# feather-power-switch-i2c-spi-breakout-mk.net
KiCad netlist of a schematic drawn in EAGLE
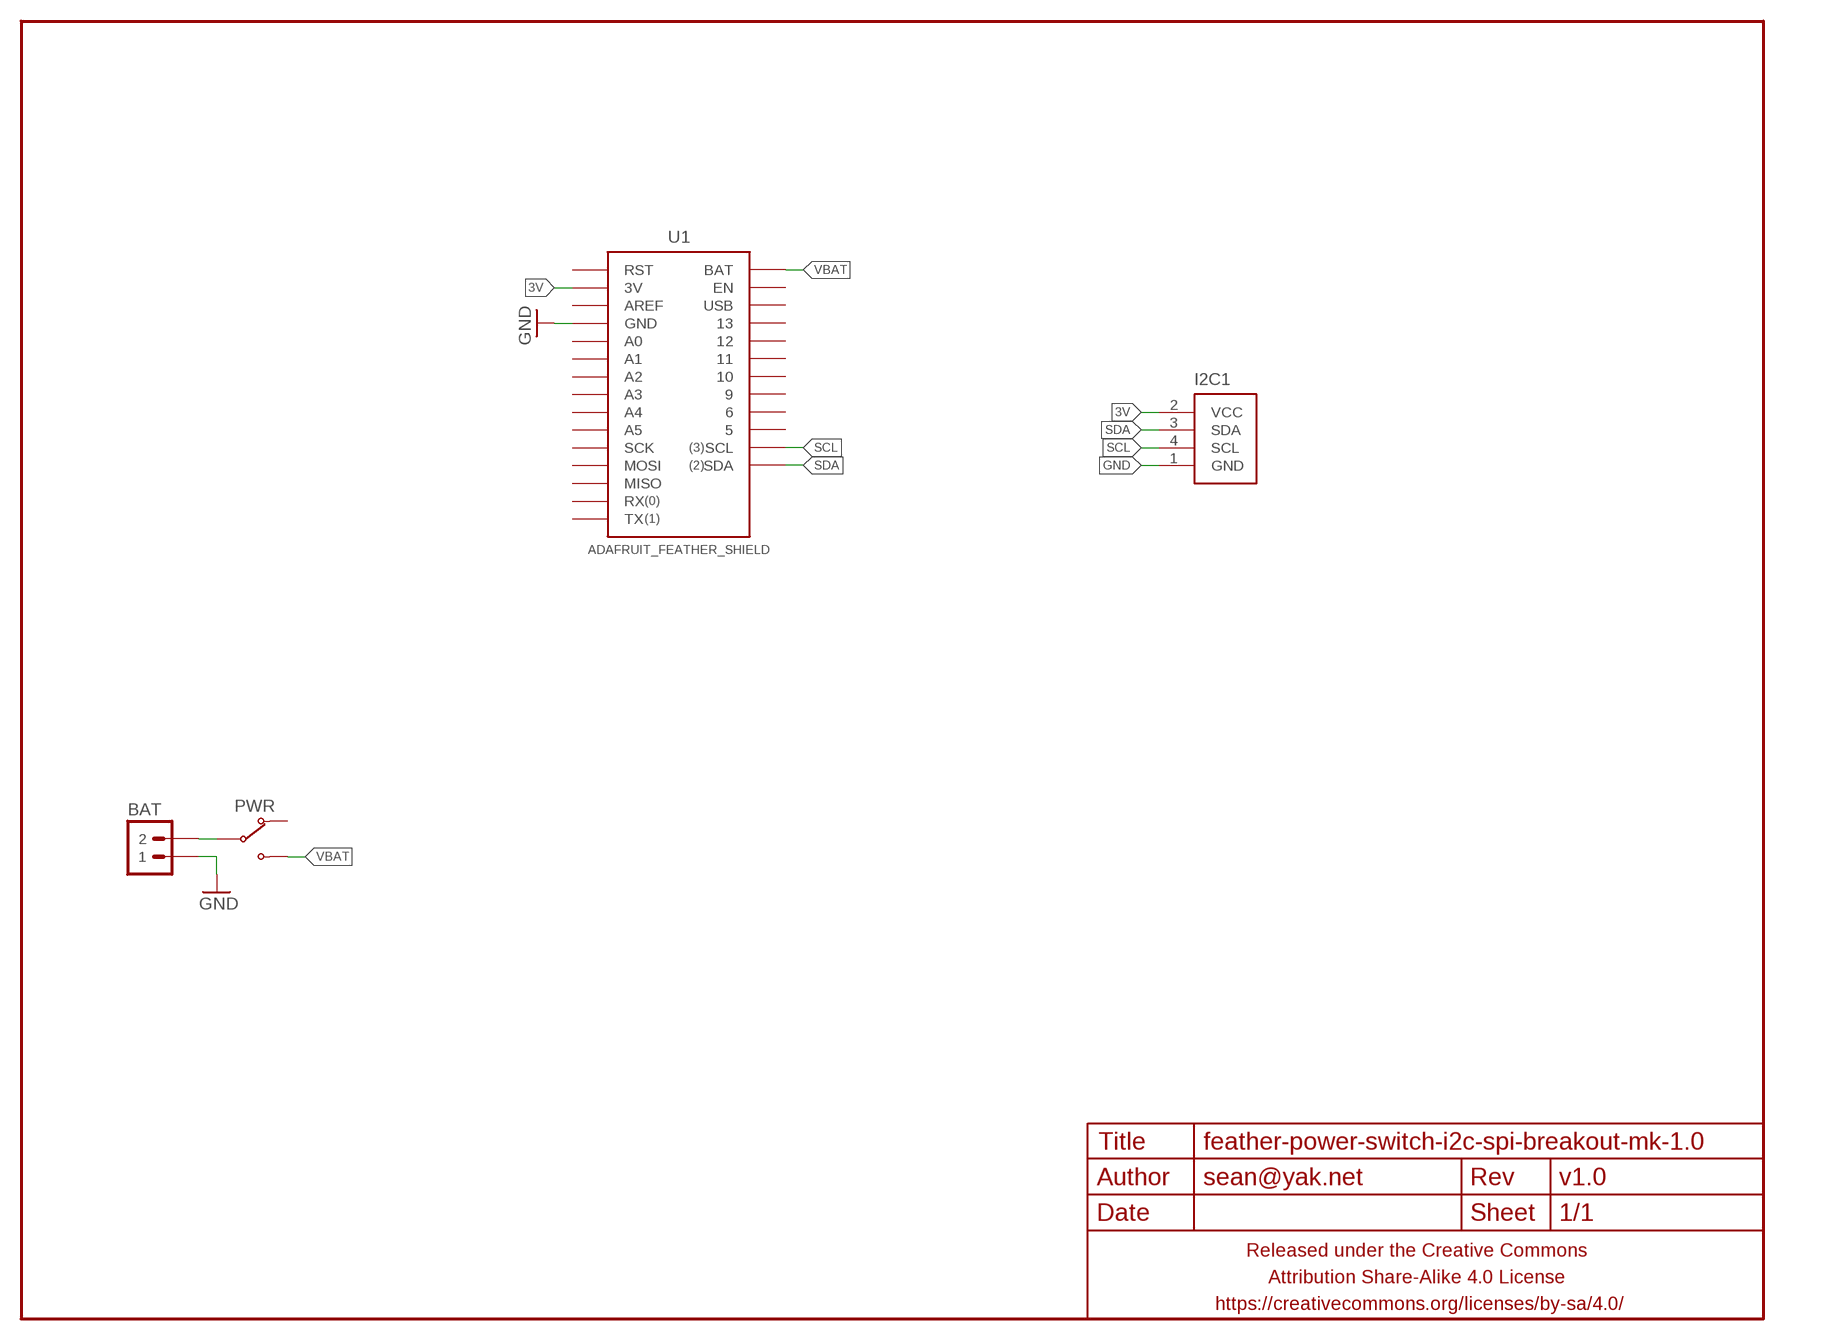
[diagram p0: schematic, sheet 1]

(export (version "E")
  (design (tool "Eeschema 10.0.6"))
  (components
    (comp (ref "BAT")
      (value "M02JST-PTH-RA-R+")
      (footprint "eagle-import:JST-2-PH-RA-PTH-R+")
      (libsource (lib "eagle-import") (part "M02JST-PTH-RA-R+"))
    )
    (comp (ref "FRAME1")
      (value "FRAME-LETTERNO_PACKAGE")
      (footprint "eagle-import:DUMMY")
      (fields (field (name "DESIGNER") "sean@yak.net") (field (name "VERSION") "v1.0"))
      (libsource (lib "eagle-import") (part "FRAME-LETTERNO_PACKAGE"))
    )
    (comp (ref "I2C1")
      (value "M04-I2CJST-4-PH-VERT-CENTERED-I2C")
      (footprint "eagle-import:JST-4-PH-VERT-PTH-CENTERED-I2C")
      (libsource (lib "eagle-import") (part "M04-I2CJST-4-PH-VERT-CENTERED-I2C"))
    )
    (comp (ref "PWR")
      (value "SWITCH-SPDTPTH-RA-2.54MM")
      (footprint "eagle-import:SPDT-RA-2.54MM")
      (libsource (lib "eagle-import") (part "SWITCH-SPDTPTH-RA-2.54MM"))
    )
    (comp (ref "U1")
      (value "ADAFRUIT_FEATHER_SHIELD")
      (footprint "eagle-import:ADAFRUIT_FEATHER")
      (libsource (lib "eagle-import") (part "ADAFRUIT_FEATHER_SHIELD"))
    )
  )
  (nets
    (net (code "1") (name "3V") (class "Default")
      (node (ref "I2C1") (pin "2") (pinfunction "VCC_2") (pintype "bidirectional"))
      (node (ref "U1") (pin "3V") (pinfunction "3V_3V") (pintype "bidirectional"))
    )
    (net (code "2") (name "GND") (class "Default")
      (node (ref "BAT") (pin "1") (pinfunction "1_1") (pintype "passive"))
      (node (ref "I2C1") (pin "1") (pinfunction "GND_1") (pintype "bidirectional"))
      (node (ref "U1") (pin "GND@0") (pinfunction "GND_GND@0") (pintype "bidirectional"))
      (node (ref "U1") (pin "GND@1") (pinfunction "GND_GND@1") (pintype "bidirectional"))
    )
    (net (code "3") (name "Net-(PWR-COM)") (class "Default")
      (node (ref "BAT") (pin "2") (pinfunction "2_2") (pintype "passive"))
      (node (ref "PWR") (pin "2") (pinfunction "COM_2") (pintype "passive"))
    )
    (net (code "4") (name "SCL") (class "Default")
      (node (ref "I2C1") (pin "4") (pinfunction "SCL_4") (pintype "bidirectional"))
      (node (ref "U1") (pin "SCL") (pinfunction "SCL_SCL") (pintype "bidirectional"))
    )
    (net (code "5") (name "SDA") (class "Default")
      (node (ref "I2C1") (pin "3") (pinfunction "SDA_3") (pintype "bidirectional"))
      (node (ref "U1") (pin "SDA") (pinfunction "SDA_SDA") (pintype "bidirectional"))
    )
    (net (code "6") (name "VBAT") (class "Default")
      (node (ref "PWR") (pin "3") (pinfunction "NO_3") (pintype "passive"))
      (node (ref "U1") (pin "BAT") (pinfunction "BAT_BAT") (pintype "bidirectional"))
    )
    (net (code "7") (name "unconnected-(PWR-NC-Pad1)") (class "Default")
      (node (ref "PWR") (pin "1") (pinfunction "NC_1") (pintype "passive"))
    )
    (net (code "8") (name "unconnected-(U1-Pad5)") (class "Default")
      (node (ref "U1") (pin "5") (pinfunction "5_5") (pintype "bidirectional"))
    )
    (net (code "9") (name "unconnected-(U1-Pad6)") (class "Default")
      (node (ref "U1") (pin "6") (pinfunction "6_6") (pintype "bidirectional"))
    )
    (net (code "10") (name "unconnected-(U1-Pad9)") (class "Default")
      (node (ref "U1") (pin "9") (pinfunction "9_9") (pintype "bidirectional"))
    )
    (net (code "11") (name "unconnected-(U1-Pad10)") (class "Default")
      (node (ref "U1") (pin "10") (pinfunction "10_10") (pintype "bidirectional"))
    )
    (net (code "12") (name "unconnected-(U1-Pad11)") (class "Default")
      (node (ref "U1") (pin "11") (pinfunction "11_11") (pintype "bidirectional"))
    )
    (net (code "13") (name "unconnected-(U1-Pad12)") (class "Default")
      (node (ref "U1") (pin "12") (pinfunction "12_12") (pintype "bidirectional"))
    )
    (net (code "14") (name "unconnected-(U1-Pad13)") (class "Default")
      (node (ref "U1") (pin "13") (pinfunction "13_13") (pintype "bidirectional"))
    )
    (net (code "15") (name "unconnected-(U1-PadA0)") (class "Default")
      (node (ref "U1") (pin "A0") (pinfunction "A0_A0") (pintype "bidirectional"))
    )
    (net (code "16") (name "unconnected-(U1-PadA1)") (class "Default")
      (node (ref "U1") (pin "A1") (pinfunction "A1_A1") (pintype "bidirectional"))
    )
    (net (code "17") (name "unconnected-(U1-PadA2)") (class "Default")
      (node (ref "U1") (pin "A2") (pinfunction "A2_A2") (pintype "bidirectional"))
    )
    (net (code "18") (name "unconnected-(U1-PadA3)") (class "Default")
      (node (ref "U1") (pin "A3") (pinfunction "A3_A3") (pintype "bidirectional"))
    )
    (net (code "19") (name "unconnected-(U1-PadA4)") (class "Default")
      (node (ref "U1") (pin "A4") (pinfunction "A4_A4") (pintype "bidirectional"))
    )
    (net (code "20") (name "unconnected-(U1-PadA5)") (class "Default")
      (node (ref "U1") (pin "A5") (pinfunction "A5_A5") (pintype "bidirectional"))
    )
    (net (code "21") (name "unconnected-(U1-PadAREF)") (class "Default")
      (node (ref "U1") (pin "AREF") (pinfunction "AREF_AREF") (pintype "bidirectional"))
    )
    (net (code "22") (name "unconnected-(U1-PadEN)") (class "Default")
      (node (ref "U1") (pin "EN") (pinfunction "EN_EN") (pintype "bidirectional"))
    )
    (net (code "23") (name "unconnected-(U1-PadMISO)") (class "Default")
      (node (ref "U1") (pin "MISO") (pinfunction "MISO_MISO") (pintype "bidirectional"))
    )
    (net (code "24") (name "unconnected-(U1-PadMOSI)") (class "Default")
      (node (ref "U1") (pin "MOSI") (pinfunction "MOSI_MOSI") (pintype "bidirectional"))
    )
    (net (code "25") (name "unconnected-(U1-PadRST)") (class "Default")
      (node (ref "U1") (pin "RST") (pinfunction "RST_RST") (pintype "bidirectional"))
    )
    (net (code "26") (name "unconnected-(U1-PadRX)") (class "Default")
      (node (ref "U1") (pin "RX") (pinfunction "RX_RX") (pintype "bidirectional"))
    )
    (net (code "27") (name "unconnected-(U1-PadSCK)") (class "Default")
      (node (ref "U1") (pin "SCK") (pinfunction "SCK_SCK") (pintype "bidirectional"))
    )
    (net (code "28") (name "unconnected-(U1-PadTX)") (class "Default")
      (node (ref "U1") (pin "TX") (pinfunction "TX_TX") (pintype "bidirectional"))
    )
    (net (code "29") (name "unconnected-(U1-PadUSB)") (class "Default")
      (node (ref "U1") (pin "USB") (pinfunction "USB_USB") (pintype "bidirectional"))
    )
  )
)
